# ENC28J60_LAN_RFID_PCB.net
KiCad netlist of a schematic drawn in EAGLE
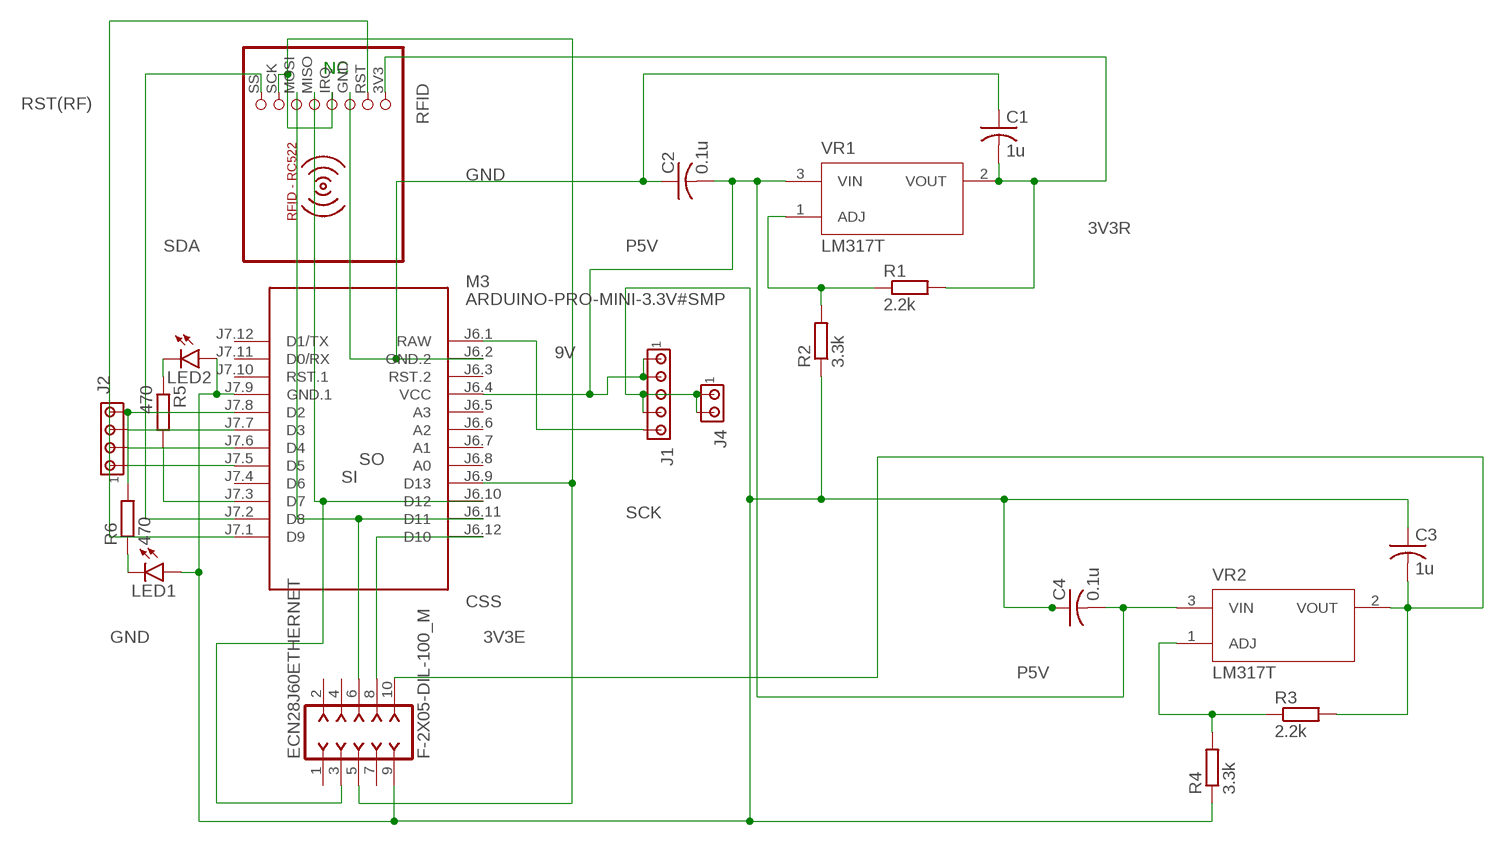
[diagram p0: schematic, sheet 1]

(export (version "E")
  (design (tool "Eeschema 10.0.6"))
  (components
    (comp (ref "C1")
      (value "1u")
      (footprint "eagle-import:C025-025X050")
      (libsource (lib "eagle-import") (part "C-US025-025X050"))
    )
    (comp (ref "C2")
      (value "0.1u")
      (footprint "eagle-import:C025-025X050")
      (libsource (lib "eagle-import") (part "C-US025-025X050"))
    )
    (comp (ref "C3")
      (value "1u")
      (footprint "eagle-import:C025-025X050")
      (libsource (lib "eagle-import") (part "C-US025-025X050"))
    )
    (comp (ref "C4")
      (value "0.1u")
      (footprint "eagle-import:C025-025X050")
      (libsource (lib "eagle-import") (part "C-US025-025X050"))
    )
    (comp (ref "ECN28J60ETHERNET")
      (value "F-2X05-DIL-100_M")
      (footprint "eagle-import:DIL-100-2X05_M")
      (libsource (lib "eagle-import") (part "F-2X05-DIL-100_M"))
    )
    (comp (ref "J1")
      (value "MTA05-100")
      (footprint "eagle-import:10X05MTA")
      (libsource (lib "eagle-import") (part "MTA05-100"))
    )
    (comp (ref "J2")
      (value "MTA04-100")
      (footprint "eagle-import:10X04MTA")
      (libsource (lib "eagle-import") (part "MTA04-100"))
    )
    (comp (ref "J4")
      (value "MTA02-100")
      (footprint "eagle-import:10X02MTA")
      (libsource (lib "eagle-import") (part "MTA02-100"))
    )
    (comp (ref "LED1")
      (value "LED3MM")
      (footprint "eagle-import:LED3MM")
      (libsource (lib "eagle-import") (part "LED3MM"))
    )
    (comp (ref "LED2")
      (value "LED3MM")
      (footprint "eagle-import:LED3MM")
      (libsource (lib "eagle-import") (part "LED3MM"))
    )
    (comp (ref "M3")
      (value "ARDUINO-PRO-MINI-3.3V#SMP")
      (footprint "eagle-import:ARDUINO-PRO-MINI#SMP")
      (libsource (lib "eagle-import") (part "ARDUINO-PRO-MINI-#SMP3.3V"))
    )
    (comp (ref "R1")
      (value "2.2k")
      (footprint "eagle-import:0207_10")
      (libsource (lib "eagle-import") (part "R-EU_0207/10"))
    )
    (comp (ref "R2")
      (value "3.3k")
      (footprint "eagle-import:0207_10")
      (libsource (lib "eagle-import") (part "R-EU_0207/10"))
    )
    (comp (ref "R3")
      (value "2.2k")
      (footprint "eagle-import:0207_10")
      (libsource (lib "eagle-import") (part "R-EU_0207/10"))
    )
    (comp (ref "R4")
      (value "3.3k")
      (footprint "eagle-import:0207_10")
      (libsource (lib "eagle-import") (part "R-EU_0207/10"))
    )
    (comp (ref "R5")
      (value "470")
      (footprint "eagle-import:0207_10")
      (libsource (lib "eagle-import") (part "R-EU_0207/10"))
    )
    (comp (ref "R6")
      (value "470")
      (footprint "eagle-import:0207_10")
      (libsource (lib "eagle-import") (part "R-EU_0207/10"))
    )
    (comp (ref "RFID")
      (value "RFID-RC522")
      (footprint "eagle-import:RFID-RC522")
      (libsource (lib "eagle-import") (part "RFID-RC522"))
    )
    (comp (ref "VR1")
      (value "LM317T")
      (footprint "eagle-import:TO254P1054X470X1955-3")
      (fields (field (name "MF") "Texas Instruments"))
      (libsource (lib "eagle-import") (part "LM317T"))
    )
    (comp (ref "VR2")
      (value "LM317T")
      (footprint "eagle-import:TO254P1054X470X1955-3")
      (fields (field (name "MF") "Texas Instruments"))
      (libsource (lib "eagle-import") (part "LM317T"))
    )
  )
  (nets
    (net (code "1") (name "/3V3E") (class "Default")
      (node (ref "C3") (pin "2") (pinfunction "2_2") (pintype "passive"))
      (node (ref "ECN28J60ETHERNET") (pin "10") (pinfunction "10_10") (pintype "passive"))
      (node (ref "R3") (pin "2") (pinfunction "2_2") (pintype "passive"))
      (node (ref "VR2") (pin "2") (pinfunction "VOUT_2") (pintype "output"))
    )
    (net (code "2") (name "/3V3R") (class "Default")
      (node (ref "C1") (pin "2") (pinfunction "2_2") (pintype "passive"))
      (node (ref "R1") (pin "2") (pinfunction "2_2") (pintype "passive"))
      (node (ref "RFID") (pin "3V3") (pinfunction "1_3V3") (pintype "passive"))
      (node (ref "VR1") (pin "2") (pinfunction "VOUT_2") (pintype "output"))
    )
    (net (code "3") (name "/9V") (class "Default")
      (node (ref "J1") (pin "5") (pinfunction "5_5") (pintype "passive"))
      (node (ref "M3") (pin "J6.1") (pinfunction "RAW_J6.1") (pintype "power_in"))
    )
    (net (code "4") (name "/CSS") (class "Default")
      (node (ref "ECN28J60ETHERNET") (pin "8") (pinfunction "8_8") (pintype "passive"))
      (node (ref "M3") (pin "J6.12") (pinfunction "D10_J6.12") (pintype "bidirectional"))
    )
    (net (code "5") (name "/GND") (class "Default")
      (node (ref "C1") (pin "1") (pinfunction "1_1") (pintype "passive"))
      (node (ref "C2") (pin "1") (pinfunction "1_1") (pintype "passive"))
      (node (ref "C3") (pin "1") (pinfunction "1_1") (pintype "passive"))
      (node (ref "C4") (pin "1") (pinfunction "1_1") (pintype "passive"))
      (node (ref "ECN28J60ETHERNET") (pin "9") (pinfunction "9_9") (pintype "passive"))
      (node (ref "J1") (pin "3") (pinfunction "3_3") (pintype "passive"))
      (node (ref "J1") (pin "4") (pinfunction "4_4") (pintype "passive"))
      (node (ref "J4") (pin "1") (pinfunction "1_1") (pintype "passive"))
      (node (ref "J4") (pin "2") (pinfunction "2_2") (pintype "passive"))
      (node (ref "LED1") (pin "A") (pinfunction "A_A") (pintype "passive"))
      (node (ref "LED2") (pin "A") (pinfunction "A_A") (pintype "passive"))
      (node (ref "M3") (pin "J6.2") (pinfunction "GND.2_J6.2") (pintype "power_in"))
      (node (ref "M3") (pin "J7.9") (pinfunction "GND.1_J7.9") (pintype "power_in"))
      (node (ref "R2") (pin "1") (pinfunction "1_1") (pintype "passive"))
      (node (ref "R4") (pin "1") (pinfunction "1_1") (pintype "passive"))
      (node (ref "RFID") (pin "GND") (pinfunction "3_GND") (pintype "passive"))
    )
    (net (code "6") (name "/P5V") (class "Default")
      (node (ref "C2") (pin "2") (pinfunction "2_2") (pintype "passive"))
      (node (ref "C4") (pin "2") (pinfunction "2_2") (pintype "passive"))
      (node (ref "J1") (pin "1") (pinfunction "1_1") (pintype "passive"))
      (node (ref "J1") (pin "2") (pinfunction "2_2") (pintype "passive"))
      (node (ref "M3") (pin "J6.4") (pinfunction "VCC_J6.4") (pintype "power_in"))
      (node (ref "VR1") (pin "3") (pinfunction "VIN_3") (pintype "input"))
      (node (ref "VR2") (pin "3") (pinfunction "VIN_3") (pintype "input"))
    )
    (net (code "7") (name "/RST(RF)") (class "Default")
      (node (ref "M3") (pin "J7.1") (pinfunction "D9_J7.1") (pintype "bidirectional"))
      (node (ref "RFID") (pin "RST") (pinfunction "2_RST") (pintype "passive"))
    )
    (net (code "8") (name "/SCK") (class "Default")
      (node (ref "ECN28J60ETHERNET") (pin "5") (pinfunction "5_5") (pintype "passive"))
      (node (ref "M3") (pin "J6.9") (pinfunction "D13_J6.9") (pintype "bidirectional"))
      (node (ref "RFID") (pin "IRQ") (pinfunction "4_IRQ") (pintype "passive"))
      (node (ref "RFID") (pin "SCK") (pinfunction "7_SCK") (pintype "passive"))
    )
    (net (code "9") (name "/SDA") (class "Default")
      (node (ref "M3") (pin "J7.2") (pinfunction "D8_J7.2") (pintype "bidirectional"))
      (node (ref "RFID") (pin "SS") (pinfunction "8_SS") (pintype "passive"))
    )
    (net (code "10") (name "/SI") (class "Default")
      (node (ref "ECN28J60ETHERNET") (pin "6") (pinfunction "6_6") (pintype "passive"))
      (node (ref "M3") (pin "J6.11") (pinfunction "D11_J6.11") (pintype "bidirectional"))
      (node (ref "RFID") (pin "MOSI") (pinfunction "6_MOSI") (pintype "passive"))
    )
    (net (code "11") (name "/SO") (class "Default")
      (node (ref "ECN28J60ETHERNET") (pin "3") (pinfunction "3_3") (pintype "passive"))
      (node (ref "M3") (pin "J6.10") (pinfunction "D12_J6.10") (pintype "bidirectional"))
      (node (ref "RFID") (pin "MISO") (pinfunction "5_MISO") (pintype "passive"))
    )
    (net (code "12") (name "Net-(LED1-C)") (class "Default")
      (node (ref "LED1") (pin "K") (pinfunction "C_K") (pintype "passive"))
      (node (ref "R6") (pin "1") (pinfunction "1_1") (pintype "passive"))
    )
    (net (code "13") (name "Net-(LED2-C)") (class "Default")
      (node (ref "LED2") (pin "K") (pinfunction "C_K") (pintype "passive"))
      (node (ref "R5") (pin "1") (pinfunction "1_1") (pintype "passive"))
    )
    (net (code "14") (name "Net-(M3-D2)") (class "Default")
      (node (ref "J2") (pin "4") (pinfunction "4_4") (pintype "passive"))
      (node (ref "M3") (pin "J7.8") (pinfunction "D2_J7.8") (pintype "bidirectional"))
      (node (ref "R6") (pin "2") (pinfunction "2_2") (pintype "passive"))
    )
    (net (code "15") (name "Net-(M3-D3)") (class "Default")
      (node (ref "J2") (pin "3") (pinfunction "3_3") (pintype "passive"))
      (node (ref "M3") (pin "J7.7") (pinfunction "D3_J7.7") (pintype "bidirectional"))
    )
    (net (code "16") (name "Net-(M3-D4)") (class "Default")
      (node (ref "J2") (pin "2") (pinfunction "2_2") (pintype "passive"))
      (node (ref "M3") (pin "J7.6") (pinfunction "D4_J7.6") (pintype "bidirectional"))
    )
    (net (code "17") (name "Net-(M3-D5)") (class "Default")
      (node (ref "J2") (pin "1") (pinfunction "1_1") (pintype "passive"))
      (node (ref "M3") (pin "J7.5") (pinfunction "D5_J7.5") (pintype "bidirectional"))
    )
    (net (code "18") (name "Net-(M3-D7)") (class "Default")
      (node (ref "M3") (pin "J7.3") (pinfunction "D7_J7.3") (pintype "bidirectional"))
      (node (ref "R5") (pin "2") (pinfunction "2_2") (pintype "passive"))
    )
    (net (code "19") (name "Net-(VR1-ADJ)") (class "Default")
      (node (ref "R1") (pin "1") (pinfunction "1_1") (pintype "passive"))
      (node (ref "R2") (pin "2") (pinfunction "2_2") (pintype "passive"))
      (node (ref "VR1") (pin "1") (pinfunction "ADJ_1") (pintype "input"))
    )
    (net (code "20") (name "Net-(VR2-ADJ)") (class "Default")
      (node (ref "R3") (pin "1") (pinfunction "1_1") (pintype "passive"))
      (node (ref "R4") (pin "2") (pinfunction "2_2") (pintype "passive"))
      (node (ref "VR2") (pin "1") (pinfunction "ADJ_1") (pintype "input"))
    )
    (net (code "21") (name "unconnected-(ECN28J60ETHERNET-Pad1)") (class "Default")
      (node (ref "ECN28J60ETHERNET") (pin "1") (pinfunction "1_1") (pintype "passive"))
    )
    (net (code "22") (name "unconnected-(ECN28J60ETHERNET-Pad2)") (class "Default")
      (node (ref "ECN28J60ETHERNET") (pin "2") (pinfunction "2_2") (pintype "passive"))
    )
    (net (code "23") (name "unconnected-(ECN28J60ETHERNET-Pad4)") (class "Default")
      (node (ref "ECN28J60ETHERNET") (pin "4") (pinfunction "4_4") (pintype "passive"))
    )
    (net (code "24") (name "unconnected-(ECN28J60ETHERNET-Pad7)") (class "Default")
      (node (ref "ECN28J60ETHERNET") (pin "7") (pinfunction "7_7") (pintype "passive"))
    )
    (net (code "25") (name "unconnected-(M3-A0-PadJ6.8)") (class "Default")
      (node (ref "M3") (pin "J6.8") (pinfunction "A0_J6.8") (pintype "bidirectional"))
    )
    (net (code "26") (name "unconnected-(M3-A1-PadJ6.7)") (class "Default")
      (node (ref "M3") (pin "J6.7") (pinfunction "A1_J6.7") (pintype "bidirectional"))
    )
    (net (code "27") (name "unconnected-(M3-A2-PadJ6.6)") (class "Default")
      (node (ref "M3") (pin "J6.6") (pinfunction "A2_J6.6") (pintype "bidirectional"))
    )
    (net (code "28") (name "unconnected-(M3-A3-PadJ6.5)") (class "Default")
      (node (ref "M3") (pin "J6.5") (pinfunction "A3_J6.5") (pintype "bidirectional"))
    )
    (net (code "29") (name "unconnected-(M3-D0{slash}RX-PadJ7.11)") (class "Default")
      (node (ref "M3") (pin "J7.11") (pinfunction "D0/RX_J7.11") (pintype "bidirectional"))
    )
    (net (code "30") (name "unconnected-(M3-D1{slash}TX-PadJ7.12)") (class "Default")
      (node (ref "M3") (pin "J7.12") (pinfunction "D1/TX_J7.12") (pintype "bidirectional"))
    )
    (net (code "31") (name "unconnected-(M3-D6-PadJ7.4)") (class "Default")
      (node (ref "M3") (pin "J7.4") (pinfunction "D6_J7.4") (pintype "bidirectional"))
    )
    (net (code "32") (name "unconnected-(M3-RST.1-PadJ7.10)") (class "Default")
      (node (ref "M3") (pin "J7.10") (pinfunction "RST.1_J7.10") (pintype "bidirectional"))
    )
    (net (code "33") (name "unconnected-(M3-RST.2-PadJ6.3)") (class "Default")
      (node (ref "M3") (pin "J6.3") (pinfunction "RST.2_J6.3") (pintype "bidirectional"))
    )
  )
)
